# CH9329.net
KiCad netlist of a schematic drawn in Altium Designer
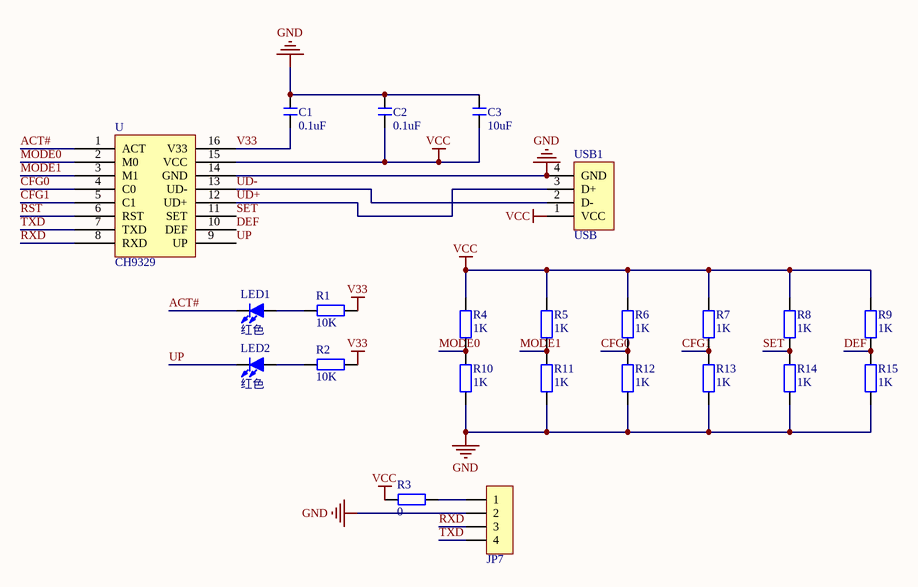
[diagram p0: CH9329.SchDoc]

(export (version "E")
  (design (tool "Eeschema 10.0.6"))
  (components
    (comp (ref "C1")
      (value "0.1uF")
      (footprint "C 0805_L")
      (description "无极性贴片电容")
      (fields (field (name "版权归属") "源创客"))
      (libsource (lib "3.1   - 电阻-电容-电感") (part "C"))
    )
    (comp (ref "C2")
      (value "0.1uF")
      (footprint "C 0805_L")
      (description "无极性贴片电容")
      (fields (field (name "版权归属") "源创客"))
      (libsource (lib "3.1   - 电阻-电容-电感") (part "C"))
    )
    (comp (ref "C3")
      (value "10uF")
      (footprint "C 0805_L")
      (description "无极性贴片电容")
      (fields (field (name "版权归属") "源创客"))
      (libsource (lib "3.1   - 电阻-电容-电感") (part "C"))
    )
    (comp (ref "JP7")
      (value "HDR-1X4")
      (footprint "HDR2.54-LI-4P")
      (description "4P接插件")
      (fields (field (name "版权归属") "源创客"))
      (libsource (lib "4.5   - 接插件-脚距2.54") (part "Header 4"))
    )
    (comp (ref "LED1")
      (value "红色")
      (footprint "LED 0805G")
      (description "贴片LED")
      (fields (field (name "版权归属") "源创客"))
      (libsource (lib "9.1   - LED") (part "LED-SMD"))
    )
    (comp (ref "LED2")
      (value "红色")
      (footprint "LED 0805G")
      (description "贴片LED")
      (fields (field (name "版权归属") "源创客"))
      (libsource (lib "9.1   - LED") (part "LED-SMD"))
    )
    (comp (ref "R1")
      (value "10K")
      (footprint "R 0805_L")
      (description "贴片电阻")
      (fields (field (name "版权归属") "源创客"))
      (libsource (lib "3.1   - 电阻-电容-电感") (part "R"))
    )
    (comp (ref "R2")
      (value "10K")
      (footprint "R 0805_L")
      (description "贴片电阻")
      (fields (field (name "版权归属") "源创客"))
      (libsource (lib "3.1   - 电阻-电容-电感") (part "R"))
    )
    (comp (ref "R3")
      (value "0")
      (footprint "R 0805_L")
      (description "贴片电阻")
      (fields (field (name "版权归属") "源创客"))
      (libsource (lib "3.1   - 电阻-电容-电感") (part "R"))
    )
    (comp (ref "R4")
      (value "1K")
      (footprint "R 0603_L")
      (description "贴片电阻")
      (fields (field (name "版权归属") "源创客"))
      (libsource (lib "3.1   - 电阻-电容-电感") (part "R"))
    )
    (comp (ref "R5")
      (value "1K")
      (footprint "R 0603_L")
      (description "贴片电阻")
      (fields (field (name "版权归属") "源创客"))
      (libsource (lib "3.1   - 电阻-电容-电感") (part "R"))
    )
    (comp (ref "R6")
      (value "1K")
      (footprint "R 0603_L")
      (description "贴片电阻")
      (fields (field (name "版权归属") "源创客"))
      (libsource (lib "3.1   - 电阻-电容-电感") (part "R"))
    )
    (comp (ref "R7")
      (value "1K")
      (footprint "R 0603_L")
      (description "贴片电阻")
      (fields (field (name "版权归属") "源创客"))
      (libsource (lib "3.1   - 电阻-电容-电感") (part "R"))
    )
    (comp (ref "R8")
      (value "1K")
      (footprint "R 0603_L")
      (description "贴片电阻")
      (fields (field (name "版权归属") "源创客"))
      (libsource (lib "3.1   - 电阻-电容-电感") (part "R"))
    )
    (comp (ref "R9")
      (value "1K")
      (footprint "R 0603_L")
      (description "贴片电阻")
      (fields (field (name "版权归属") "源创客"))
      (libsource (lib "3.1   - 电阻-电容-电感") (part "R"))
    )
    (comp (ref "R10")
      (value "1K")
      (footprint "R 0603_L")
      (description "贴片电阻")
      (fields (field (name "版权归属") "源创客"))
      (libsource (lib "3.1   - 电阻-电容-电感") (part "R"))
    )
    (comp (ref "R11")
      (value "1K")
      (footprint "R 0603_L")
      (description "贴片电阻")
      (fields (field (name "版权归属") "源创客"))
      (libsource (lib "3.1   - 电阻-电容-电感") (part "R"))
    )
    (comp (ref "R12")
      (value "1K")
      (footprint "R 0603_L")
      (description "贴片电阻")
      (fields (field (name "版权归属") "源创客"))
      (libsource (lib "3.1   - 电阻-电容-电感") (part "R"))
    )
    (comp (ref "R13")
      (value "1K")
      (footprint "R 0603_L")
      (description "贴片电阻")
      (fields (field (name "版权归属") "源创客"))
      (libsource (lib "3.1   - 电阻-电容-电感") (part "R"))
    )
    (comp (ref "R14")
      (value "1K")
      (footprint "R 0603_L")
      (description "贴片电阻")
      (fields (field (name "版权归属") "源创客"))
      (libsource (lib "3.1   - 电阻-电容-电感") (part "R"))
    )
    (comp (ref "R15")
      (value "1K")
      (footprint "R 0603_L")
      (description "贴片电阻")
      (fields (field (name "版权归属") "源创客"))
      (libsource (lib "3.1   - 电阻-电容-电感") (part "R"))
    )
    (comp (ref "U") (value "CH9329") (footprint "ch9329") (libsource (lib "ch9329") (part "CH9329")))
    (comp (ref "USB1")
      (value "USB")
      (footprint "USB_A/P_A")
      (description "USB-A型公接口")
      (fields (field (name "版权归属") "源创客"))
      (libsource (lib "4.1   - 接口类") (part "USB-A/P"))
    )
  )
  (nets
    (net (code "1") (name "/ACT#") (class "Default")
      (node (ref "LED1") (pin "2") (pinfunction "K_2") (pintype "passive"))
      (node (ref "U") (pin "1") (pinfunction "ACT_1") (pintype "passive"))
    )
    (net (code "2") (name "/CFG0") (class "Default")
      (node (ref "R12") (pin "2") (pinfunction "2_2") (pintype "passive"))
      (node (ref "R6") (pin "1") (pinfunction "1_1") (pintype "passive"))
      (node (ref "U") (pin "4") (pinfunction "C0_4") (pintype "passive"))
    )
    (net (code "3") (name "/CFG1") (class "Default")
      (node (ref "R13") (pin "2") (pinfunction "2_2") (pintype "passive"))
      (node (ref "R7") (pin "1") (pinfunction "1_1") (pintype "passive"))
      (node (ref "U") (pin "5") (pinfunction "C1_5") (pintype "passive"))
    )
    (net (code "4") (name "/DEF") (class "Default")
      (node (ref "R15") (pin "2") (pinfunction "2_2") (pintype "passive"))
      (node (ref "R9") (pin "1") (pinfunction "1_1") (pintype "passive"))
      (node (ref "U") (pin "10") (pinfunction "DEF_10") (pintype "passive"))
    )
    (net (code "5") (name "/MODE0") (class "Default")
      (node (ref "R10") (pin "2") (pinfunction "2_2") (pintype "passive"))
      (node (ref "R4") (pin "1") (pinfunction "1_1") (pintype "passive"))
      (node (ref "U") (pin "2") (pinfunction "M0_2") (pintype "passive"))
    )
    (net (code "6") (name "/MODE1") (class "Default")
      (node (ref "R11") (pin "2") (pinfunction "2_2") (pintype "passive"))
      (node (ref "R5") (pin "1") (pinfunction "1_1") (pintype "passive"))
      (node (ref "U") (pin "3") (pinfunction "M1_3") (pintype "passive"))
    )
    (net (code "7") (name "/RST") (class "Default")
      (node (ref "U") (pin "6") (pinfunction "RST_6") (pintype "passive"))
    )
    (net (code "8") (name "/RXD") (class "Default")
      (node (ref "JP7") (pin "3") (pinfunction "3_3") (pintype "passive"))
      (node (ref "U") (pin "8") (pinfunction "RXD_8") (pintype "passive"))
    )
    (net (code "9") (name "/SET") (class "Default")
      (node (ref "R14") (pin "2") (pinfunction "2_2") (pintype "passive"))
      (node (ref "R8") (pin "1") (pinfunction "1_1") (pintype "passive"))
      (node (ref "U") (pin "11") (pinfunction "SET_11") (pintype "passive"))
    )
    (net (code "10") (name "/TXD") (class "Default")
      (node (ref "JP7") (pin "4") (pinfunction "4_4") (pintype "passive"))
      (node (ref "U") (pin "7") (pinfunction "TXD_7") (pintype "passive"))
    )
    (net (code "11") (name "/UD+") (class "Default")
      (node (ref "U") (pin "12") (pinfunction "UD+_12") (pintype "passive"))
      (node (ref "USB1") (pin "3") (pinfunction "D+_3") (pintype "passive"))
    )
    (net (code "12") (name "/UD-") (class "Default")
      (node (ref "U") (pin "13") (pinfunction "UD-_13") (pintype "passive"))
      (node (ref "USB1") (pin "2") (pinfunction "D-_2") (pintype "passive"))
    )
    (net (code "13") (name "/UP") (class "Default")
      (node (ref "LED2") (pin "2") (pinfunction "K_2") (pintype "passive"))
      (node (ref "U") (pin "9") (pinfunction "UP_9") (pintype "passive"))
    )
    (net (code "14") (name "GND") (class "Default")
      (node (ref "C1") (pin "1") (pinfunction "1_1") (pintype "passive"))
      (node (ref "C2") (pin "1") (pinfunction "1_1") (pintype "passive"))
      (node (ref "C3") (pin "1") (pinfunction "1_1") (pintype "passive"))
      (node (ref "JP7") (pin "2") (pinfunction "2_2") (pintype "passive"))
      (node (ref "R10") (pin "1") (pinfunction "1_1") (pintype "passive"))
      (node (ref "R11") (pin "1") (pinfunction "1_1") (pintype "passive"))
      (node (ref "R12") (pin "1") (pinfunction "1_1") (pintype "passive"))
      (node (ref "R13") (pin "1") (pinfunction "1_1") (pintype "passive"))
      (node (ref "R14") (pin "1") (pinfunction "1_1") (pintype "passive"))
      (node (ref "R15") (pin "1") (pinfunction "1_1") (pintype "passive"))
      (node (ref "U") (pin "14") (pinfunction "GND_14") (pintype "passive"))
      (node (ref "USB1") (pin "4") (pinfunction "GND_4") (pintype "passive"))
    )
    (net (code "15") (name "Net-(JP7-Pad1)") (class "Default")
      (node (ref "JP7") (pin "1") (pinfunction "1_1") (pintype "passive"))
      (node (ref "R3") (pin "2") (pinfunction "2_2") (pintype "passive"))
    )
    (net (code "16") (name "Net-(LED1-A)") (class "Default")
      (node (ref "LED1") (pin "1") (pinfunction "A_1") (pintype "passive"))
      (node (ref "R1") (pin "1") (pinfunction "1_1") (pintype "passive"))
    )
    (net (code "17") (name "Net-(LED2-A)") (class "Default")
      (node (ref "LED2") (pin "1") (pinfunction "A_1") (pintype "passive"))
      (node (ref "R2") (pin "1") (pinfunction "1_1") (pintype "passive"))
    )
    (net (code "18") (name "V33") (class "Default")
      (node (ref "C1") (pin "2") (pinfunction "2_2") (pintype "passive"))
      (node (ref "R1") (pin "2") (pinfunction "2_2") (pintype "passive"))
      (node (ref "R2") (pin "2") (pinfunction "2_2") (pintype "passive"))
      (node (ref "U") (pin "16") (pinfunction "V33_16") (pintype "passive"))
    )
    (net (code "19") (name "VCC") (class "Default")
      (node (ref "C2") (pin "2") (pinfunction "2_2") (pintype "passive"))
      (node (ref "C3") (pin "2") (pinfunction "2_2") (pintype "passive"))
      (node (ref "R3") (pin "1") (pinfunction "1_1") (pintype "passive"))
      (node (ref "R4") (pin "2") (pinfunction "2_2") (pintype "passive"))
      (node (ref "R5") (pin "2") (pinfunction "2_2") (pintype "passive"))
      (node (ref "R6") (pin "2") (pinfunction "2_2") (pintype "passive"))
      (node (ref "R7") (pin "2") (pinfunction "2_2") (pintype "passive"))
      (node (ref "R8") (pin "2") (pinfunction "2_2") (pintype "passive"))
      (node (ref "R9") (pin "2") (pinfunction "2_2") (pintype "passive"))
      (node (ref "U") (pin "15") (pinfunction "VCC_15") (pintype "passive"))
      (node (ref "USB1") (pin "1") (pinfunction "VCC_1") (pintype "passive"))
    )
  )
)
